# untitled.net
KiCad netlist of a schematic drawn in EAGLE
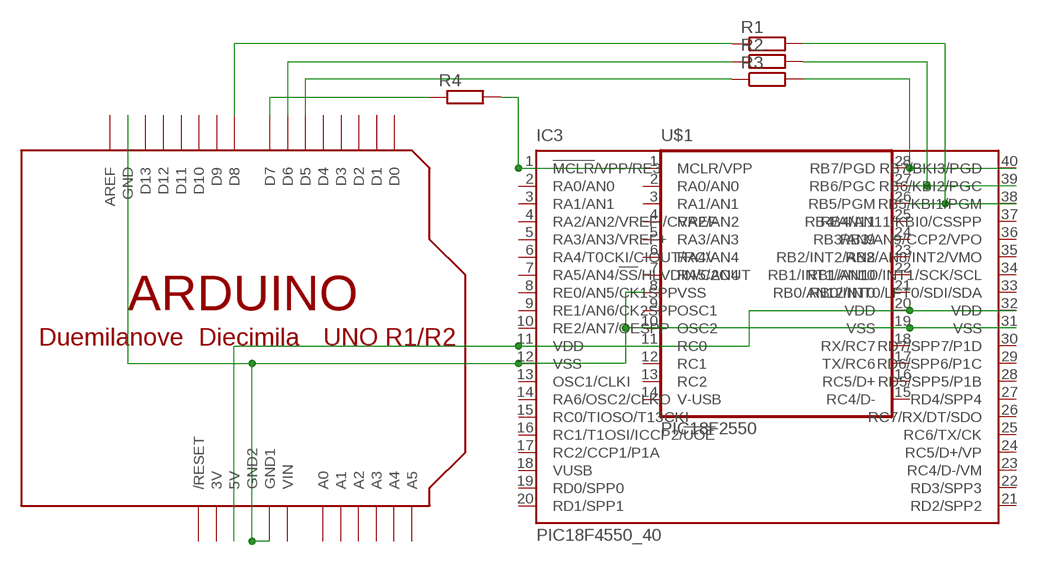
[diagram p0: schematic, sheet 1]

(export (version "E")
  (design (tool "Eeschema 10.0.6"))
  (components
    (comp (ref "IC3")
      (value "PIC18F4550_40")
      (footprint "eagle-import:DIL40")
      (fields (field (name "MF") "MICROCHIP") (field (name "MPN") "PIC18F4550-I/P"))
      (libsource (lib "eagle-import") (part "PIC18F4_40550"))
    )
    (comp (ref "R1")
      (value "R-EU_0204/7")
      (footprint "eagle-import:0204_7")
      (libsource (lib "eagle-import") (part "R-EU_0204/7"))
    )
    (comp (ref "R2")
      (value "R-EU_0204/7")
      (footprint "eagle-import:0204_7")
      (libsource (lib "eagle-import") (part "R-EU_0204/7"))
    )
    (comp (ref "R3")
      (value "R-EU_0204/7")
      (footprint "eagle-import:0204_7")
      (libsource (lib "eagle-import") (part "R-EU_0204/7"))
    )
    (comp (ref "R4")
      (value "R-EU_0204/7")
      (footprint "eagle-import:0204_7")
      (libsource (lib "eagle-import") (part "R-EU_0204/7"))
    )
    (comp (ref "U$1")
      (value "PIC18F2550")
      (footprint "eagle-import:DIL28-3")
      (libsource (lib "eagle-import") (part "PIC18F2550"))
    )
    (comp (ref "U$2")
      (value "ARDUINO-NOHOLE")
      (footprint "eagle-import:ARDUINO-NOHOLE")
      (libsource (lib "eagle-import") (part "ARDUINO-NOHOLE"))
    )
  )
  (nets
    (net (code "1") (name "/3V") (class "Default")
      (node (ref "U$2") (pin "3V") (pinfunction "3V_3V") (pintype "power_in"))
    )
    (net (code "2") (name "/VIN") (class "Default")
      (node (ref "U$2") (pin "VIN") (pinfunction "VIN_VIN") (pintype "power_in"))
    )
    (net (code "3") (name "Net-(IC3-RB5{slash}KBI1{slash}PGM)") (class "Default")
      (node (ref "IC3") (pin "38") (pinfunction "RB5/KBI1/PGM_38") (pintype "bidirectional"))
      (node (ref "R1") (pin "2") (pinfunction "2_2") (pintype "passive"))
      (node (ref "U$1") (pin "26") (pinfunction "RB5/PGM_26") (pintype "bidirectional"))
    )
    (net (code "4") (name "Net-(IC3-RB6{slash}KBI2{slash}PGC)") (class "Default")
      (node (ref "IC3") (pin "39") (pinfunction "RB6/KBI2/PGC_39") (pintype "bidirectional"))
      (node (ref "R2") (pin "2") (pinfunction "2_2") (pintype "passive"))
      (node (ref "U$1") (pin "27") (pinfunction "RB6/PGC_27") (pintype "bidirectional"))
    )
    (net (code "5") (name "Net-(IC3-RB7{slash}BKI3{slash}PGD)") (class "Default")
      (node (ref "IC3") (pin "40") (pinfunction "RB7/BKI3/PGD_40") (pintype "bidirectional"))
      (node (ref "R3") (pin "2") (pinfunction "2_2") (pintype "passive"))
      (node (ref "U$1") (pin "28") (pinfunction "RB7/PGD_28") (pintype "bidirectional"))
    )
    (net (code "6") (name "Net-(IC3-VSS-Pad12)") (class "Default")
      (node (ref "IC3") (pin "12") (pinfunction "VSS_12") (pintype "power_in"))
      (node (ref "IC3") (pin "31") (pinfunction "VSS_31") (pintype "power_in"))
      (node (ref "U$1") (pin "19") (pinfunction "VSS_19") (pintype "power_in"))
      (node (ref "U$1") (pin "8") (pinfunction "VSS_8") (pintype "power_in"))
      (node (ref "U$2") (pin "GND") (pinfunction "GND_GND") (pintype "power_in"))
      (node (ref "U$2") (pin "GND1") (pinfunction "GND1_GND1") (pintype "power_in"))
      (node (ref "U$2") (pin "GND2") (pinfunction "GND2_GND2") (pintype "power_in"))
    )
    (net (code "7") (name "Net-(IC3-~{MCLR}{slash}VPP{slash}RE3)") (class "Default")
      (node (ref "IC3") (pin "1") (pinfunction "~{MCLR}/VPP/RE3_1") (pintype "input"))
      (node (ref "R4") (pin "2") (pinfunction "2_2") (pintype "passive"))
      (node (ref "U$1") (pin "1") (pinfunction "MCLR/VPP_1") (pintype "bidirectional"))
    )
    (net (code "8") (name "Net-(R1-Pad1)") (class "Default")
      (node (ref "R1") (pin "1") (pinfunction "1_1") (pintype "passive"))
      (node (ref "U$2") (pin "D8") (pinfunction "D8_D8") (pintype "bidirectional"))
    )
    (net (code "9") (name "Net-(R2-Pad1)") (class "Default")
      (node (ref "R2") (pin "1") (pinfunction "1_1") (pintype "passive"))
      (node (ref "U$2") (pin "D6") (pinfunction "D6_D6") (pintype "bidirectional"))
    )
    (net (code "10") (name "Net-(R3-Pad1)") (class "Default")
      (node (ref "R3") (pin "1") (pinfunction "1_1") (pintype "passive"))
      (node (ref "U$2") (pin "D5") (pinfunction "D5_D5") (pintype "bidirectional"))
    )
    (net (code "11") (name "Net-(R4-Pad1)") (class "Default")
      (node (ref "R4") (pin "1") (pinfunction "1_1") (pintype "passive"))
      (node (ref "U$2") (pin "D7") (pinfunction "D7_D7") (pintype "bidirectional"))
    )
    (net (code "12") (name "Net-(U$1-VDD)") (class "Default")
      (node (ref "IC3") (pin "11") (pinfunction "VDD_11") (pintype "power_in"))
      (node (ref "IC3") (pin "32") (pinfunction "VDD_32") (pintype "power_in"))
      (node (ref "U$1") (pin "20") (pinfunction "VDD_20") (pintype "power_in"))
      (node (ref "U$2") (pin "5V") (pinfunction "5V_5V") (pintype "power_in"))
    )
    (net (code "13") (name "unconnected-(IC3-OSC1{slash}CLKI-Pad13)") (class "Default")
      (node (ref "IC3") (pin "13") (pinfunction "OSC1/CLKI_13") (pintype "input"))
    )
    (net (code "14") (name "unconnected-(IC3-RA0{slash}AN0-Pad2)") (class "Default")
      (node (ref "IC3") (pin "2") (pinfunction "RA0/AN0_2") (pintype "bidirectional"))
    )
    (net (code "15") (name "unconnected-(IC3-RA1{slash}AN1-Pad3)") (class "Default")
      (node (ref "IC3") (pin "3") (pinfunction "RA1/AN1_3") (pintype "bidirectional"))
    )
    (net (code "16") (name "unconnected-(IC3-RA2{slash}AN2{slash}VREF-{slash}CVREF-Pad4)") (class "Default")
      (node (ref "IC3") (pin "4") (pinfunction "RA2/AN2/VREF-/CVREF_4") (pintype "bidirectional"))
    )
    (net (code "17") (name "unconnected-(IC3-RA3{slash}AN3{slash}VREF+-Pad5)") (class "Default")
      (node (ref "IC3") (pin "5") (pinfunction "RA3/AN3/VREF+_5") (pintype "bidirectional"))
    )
    (net (code "18") (name "unconnected-(IC3-RA4{slash}T0CKI{slash}CIOUT{slash}RCV-Pad6)") (class "Default")
      (node (ref "IC3") (pin "6") (pinfunction "RA4/T0CKI/CIOUT/RCV_6") (pintype "bidirectional"))
    )
    (net (code "19") (name "unconnected-(IC3-RA5{slash}AN4{slash}~{SS}{slash}HLVDIN{slash}C2OUT-Pad7)") (class "Default")
      (node (ref "IC3") (pin "7") (pinfunction "RA5/AN4/~{SS}/HLVDIN/C2OUT_7") (pintype "bidirectional"))
    )
    (net (code "20") (name "unconnected-(IC3-RA6{slash}OSC2{slash}CLKO-Pad14)") (class "Default")
      (node (ref "IC3") (pin "14") (pinfunction "RA6/OSC2/CLKO_14") (pintype "output"))
    )
    (net (code "21") (name "unconnected-(IC3-RB0{slash}AN12{slash}INT0{slash}LFT0{slash}SDI{slash}SDA-Pad33)") (class "Default")
      (node (ref "IC3") (pin "33") (pinfunction "RB0/AN12/INT0/LFT0/SDI/SDA_33") (pintype "bidirectional"))
    )
    (net (code "22") (name "unconnected-(IC3-RB1{slash}AN10{slash}INT1{slash}SCK{slash}SCL-Pad34)") (class "Default")
      (node (ref "IC3") (pin "34") (pinfunction "RB1/AN10/INT1/SCK/SCL_34") (pintype "bidirectional"))
    )
    (net (code "23") (name "unconnected-(IC3-RB2{slash}AN8{slash}INT2{slash}VMO-Pad35)") (class "Default")
      (node (ref "IC3") (pin "35") (pinfunction "RB2/AN8/INT2/VMO_35") (pintype "bidirectional"))
    )
    (net (code "24") (name "unconnected-(IC3-RB3{slash}AN9{slash}CCP2{slash}VPO-Pad36)") (class "Default")
      (node (ref "IC3") (pin "36") (pinfunction "RB3/AN9/CCP2/VPO_36") (pintype "bidirectional"))
    )
    (net (code "25") (name "unconnected-(IC3-RB4{slash}AN11{slash}KBI0{slash}CSSPP-Pad37)") (class "Default")
      (node (ref "IC3") (pin "37") (pinfunction "RB4/AN11/KBI0/CSSPP_37") (pintype "bidirectional"))
    )
    (net (code "26") (name "unconnected-(IC3-RC0{slash}TIOSO{slash}T13CKI-Pad15)") (class "Default")
      (node (ref "IC3") (pin "15") (pinfunction "RC0/TIOSO/T13CKI_15") (pintype "bidirectional"))
    )
    (net (code "27") (name "unconnected-(IC3-RC1{slash}T1OSI{slash}ICCP2{slash}~{UOE}-Pad16)") (class "Default")
      (node (ref "IC3") (pin "16") (pinfunction "RC1/T1OSI/ICCP2/~{UOE}_16") (pintype "bidirectional"))
    )
    (net (code "28") (name "unconnected-(IC3-RC2{slash}CCP1{slash}P1A-Pad17)") (class "Default")
      (node (ref "IC3") (pin "17") (pinfunction "RC2/CCP1/P1A_17") (pintype "bidirectional"))
    )
    (net (code "29") (name "unconnected-(IC3-RC4{slash}D-{slash}VM-Pad23)") (class "Default")
      (node (ref "IC3") (pin "23") (pinfunction "RC4/D-/VM_23") (pintype "bidirectional"))
    )
    (net (code "30") (name "unconnected-(IC3-RC5{slash}D+{slash}VP-Pad24)") (class "Default")
      (node (ref "IC3") (pin "24") (pinfunction "RC5/D+/VP_24") (pintype "bidirectional"))
    )
    (net (code "31") (name "unconnected-(IC3-RC6{slash}TX{slash}CK-Pad25)") (class "Default")
      (node (ref "IC3") (pin "25") (pinfunction "RC6/TX/CK_25") (pintype "bidirectional"))
    )
    (net (code "32") (name "unconnected-(IC3-RC7{slash}RX{slash}DT{slash}SDO-Pad26)") (class "Default")
      (node (ref "IC3") (pin "26") (pinfunction "RC7/RX/DT/SDO_26") (pintype "bidirectional"))
    )
    (net (code "33") (name "unconnected-(IC3-RD0{slash}SPP0-Pad19)") (class "Default")
      (node (ref "IC3") (pin "19") (pinfunction "RD0/SPP0_19") (pintype "bidirectional"))
    )
    (net (code "34") (name "unconnected-(IC3-RD1{slash}SPP1-Pad20)") (class "Default")
      (node (ref "IC3") (pin "20") (pinfunction "RD1/SPP1_20") (pintype "bidirectional"))
    )
    (net (code "35") (name "unconnected-(IC3-RD2{slash}SPP2-Pad21)") (class "Default")
      (node (ref "IC3") (pin "21") (pinfunction "RD2/SPP2_21") (pintype "bidirectional"))
    )
    (net (code "36") (name "unconnected-(IC3-RD3{slash}SPP3-Pad22)") (class "Default")
      (node (ref "IC3") (pin "22") (pinfunction "RD3/SPP3_22") (pintype "bidirectional"))
    )
    (net (code "37") (name "unconnected-(IC3-RD4{slash}SPP4-Pad27)") (class "Default")
      (node (ref "IC3") (pin "27") (pinfunction "RD4/SPP4_27") (pintype "bidirectional"))
    )
    (net (code "38") (name "unconnected-(IC3-RD5{slash}SPP5{slash}P1B-Pad28)") (class "Default")
      (node (ref "IC3") (pin "28") (pinfunction "RD5/SPP5/P1B_28") (pintype "bidirectional"))
    )
    (net (code "39") (name "unconnected-(IC3-RD6{slash}SPP6{slash}P1C-Pad29)") (class "Default")
      (node (ref "IC3") (pin "29") (pinfunction "RD6/SPP6/P1C_29") (pintype "bidirectional"))
    )
    (net (code "40") (name "unconnected-(IC3-RD7{slash}SPP7{slash}P1D-Pad30)") (class "Default")
      (node (ref "IC3") (pin "30") (pinfunction "RD7/SPP7/P1D_30") (pintype "bidirectional"))
    )
    (net (code "41") (name "unconnected-(IC3-RE0{slash}AN5{slash}CK1SPP-Pad8)") (class "Default")
      (node (ref "IC3") (pin "8") (pinfunction "RE0/AN5/CK1SPP_8") (pintype "bidirectional"))
    )
    (net (code "42") (name "unconnected-(IC3-RE1{slash}AN6{slash}CK2SPP-Pad9)") (class "Default")
      (node (ref "IC3") (pin "9") (pinfunction "RE1/AN6/CK2SPP_9") (pintype "bidirectional"))
    )
    (net (code "43") (name "unconnected-(IC3-RE2{slash}AN7{slash}OESPP-Pad10)") (class "Default")
      (node (ref "IC3") (pin "10") (pinfunction "RE2/AN7/OESPP_10") (pintype "bidirectional"))
    )
    (net (code "44") (name "unconnected-(IC3-VUSB-Pad18)") (class "Default")
      (node (ref "IC3") (pin "18") (pinfunction "VUSB_18") (pintype "bidirectional"))
    )
    (net (code "45") (name "unconnected-(U$1-OSC1-Pad9)") (class "Default")
      (node (ref "U$1") (pin "9") (pinfunction "OSC1_9") (pintype "bidirectional"))
    )
    (net (code "46") (name "unconnected-(U$1-OSC2-Pad10)") (class "Default")
      (node (ref "U$1") (pin "10") (pinfunction "OSC2_10") (pintype "bidirectional"))
    )
    (net (code "47") (name "unconnected-(U$1-RA0{slash}AN0-Pad2)") (class "Default")
      (node (ref "U$1") (pin "2") (pinfunction "RA0/AN0_2") (pintype "bidirectional"))
    )
    (net (code "48") (name "unconnected-(U$1-RA1{slash}AN1-Pad3)") (class "Default")
      (node (ref "U$1") (pin "3") (pinfunction "RA1/AN1_3") (pintype "bidirectional"))
    )
    (net (code "49") (name "unconnected-(U$1-RA2{slash}AN2-Pad4)") (class "Default")
      (node (ref "U$1") (pin "4") (pinfunction "RA2/AN2_4") (pintype "bidirectional"))
    )
    (net (code "50") (name "unconnected-(U$1-RA3{slash}AN3-Pad5)") (class "Default")
      (node (ref "U$1") (pin "5") (pinfunction "RA3/AN3_5") (pintype "bidirectional"))
    )
    (net (code "51") (name "unconnected-(U$1-RA4{slash}AN4-Pad6)") (class "Default")
      (node (ref "U$1") (pin "6") (pinfunction "RA4/AN4_6") (pintype "bidirectional"))
    )
    (net (code "52") (name "unconnected-(U$1-RA5{slash}AN4-Pad7)") (class "Default")
      (node (ref "U$1") (pin "7") (pinfunction "RA5/AN4_7") (pintype "bidirectional"))
    )
    (net (code "53") (name "unconnected-(U$1-RB0{slash}INT0-Pad21)") (class "Default")
      (node (ref "U$1") (pin "21") (pinfunction "RB0/INT0_21") (pintype "bidirectional"))
    )
    (net (code "54") (name "unconnected-(U$1-RB1{slash}INT1{slash}AN10-Pad22)") (class "Default")
      (node (ref "U$1") (pin "22") (pinfunction "RB1/INT1/AN10_22") (pintype "bidirectional"))
    )
    (net (code "55") (name "unconnected-(U$1-RB2{slash}INT2{slash}AN8-Pad23)") (class "Default")
      (node (ref "U$1") (pin "23") (pinfunction "RB2/INT2/AN8_23") (pintype "bidirectional"))
    )
    (net (code "56") (name "unconnected-(U$1-RB3{slash}AN9-Pad24)") (class "Default")
      (node (ref "U$1") (pin "24") (pinfunction "RB3/AN9_24") (pintype "bidirectional"))
    )
    (net (code "57") (name "unconnected-(U$1-RB4{slash}AN11-Pad25)") (class "Default")
      (node (ref "U$1") (pin "25") (pinfunction "RB4/AN11_25") (pintype "bidirectional"))
    )
    (net (code "58") (name "unconnected-(U$1-RC0-Pad11)") (class "Default")
      (node (ref "U$1") (pin "11") (pinfunction "RC0_11") (pintype "bidirectional"))
    )
    (net (code "59") (name "unconnected-(U$1-RC1-Pad12)") (class "Default")
      (node (ref "U$1") (pin "12") (pinfunction "RC1_12") (pintype "bidirectional"))
    )
    (net (code "60") (name "unconnected-(U$1-RC2-Pad13)") (class "Default")
      (node (ref "U$1") (pin "13") (pinfunction "RC2_13") (pintype "bidirectional"))
    )
    (net (code "61") (name "unconnected-(U$1-RC4{slash}D--Pad15)") (class "Default")
      (node (ref "U$1") (pin "15") (pinfunction "RC4/D-_15") (pintype "bidirectional"))
    )
    (net (code "62") (name "unconnected-(U$1-RC5{slash}D+-Pad16)") (class "Default")
      (node (ref "U$1") (pin "16") (pinfunction "RC5/D+_16") (pintype "bidirectional"))
    )
    (net (code "63") (name "unconnected-(U$1-RX{slash}RC7-Pad18)") (class "Default")
      (node (ref "U$1") (pin "18") (pinfunction "RX/RC7_18") (pintype "input"))
    )
    (net (code "64") (name "unconnected-(U$1-TX{slash}RC6-Pad17)") (class "Default")
      (node (ref "U$1") (pin "17") (pinfunction "TX/RC6_17") (pintype "bidirectional"))
    )
    (net (code "65") (name "unconnected-(U$1-V-USB-Pad14)") (class "Default")
      (node (ref "U$1") (pin "14") (pinfunction "V-USB_14") (pintype "bidirectional"))
    )
    (net (code "66") (name "unconnected-(U$2-PadA0)") (class "Default")
      (node (ref "U$2") (pin "A0") (pinfunction "A0_A0") (pintype "bidirectional"))
    )
    (net (code "67") (name "unconnected-(U$2-PadA1)") (class "Default")
      (node (ref "U$2") (pin "A1") (pinfunction "A1_A1") (pintype "bidirectional"))
    )
    (net (code "68") (name "unconnected-(U$2-PadA2)") (class "Default")
      (node (ref "U$2") (pin "A2") (pinfunction "A2_A2") (pintype "bidirectional"))
    )
    (net (code "69") (name "unconnected-(U$2-PadA3)") (class "Default")
      (node (ref "U$2") (pin "A3") (pinfunction "A3_A3") (pintype "bidirectional"))
    )
    (net (code "70") (name "unconnected-(U$2-PadA4)") (class "Default")
      (node (ref "U$2") (pin "A4") (pinfunction "A4_A4") (pintype "bidirectional"))
    )
    (net (code "71") (name "unconnected-(U$2-PadA5)") (class "Default")
      (node (ref "U$2") (pin "A5") (pinfunction "A5_A5") (pintype "bidirectional"))
    )
    (net (code "72") (name "unconnected-(U$2-PadAREF)") (class "Default")
      (node (ref "U$2") (pin "AREF") (pinfunction "AREF_AREF") (pintype "bidirectional"))
    )
    (net (code "73") (name "unconnected-(U$2-PadD0)") (class "Default")
      (node (ref "U$2") (pin "D0") (pinfunction "D0_D0") (pintype "bidirectional"))
    )
    (net (code "74") (name "unconnected-(U$2-PadD1)") (class "Default")
      (node (ref "U$2") (pin "D1") (pinfunction "D1_D1") (pintype "bidirectional"))
    )
    (net (code "75") (name "unconnected-(U$2-PadD2)") (class "Default")
      (node (ref "U$2") (pin "D2") (pinfunction "D2_D2") (pintype "bidirectional"))
    )
    (net (code "76") (name "unconnected-(U$2-PadD3)") (class "Default")
      (node (ref "U$2") (pin "D3") (pinfunction "D3_D3") (pintype "bidirectional"))
    )
    (net (code "77") (name "unconnected-(U$2-PadD4)") (class "Default")
      (node (ref "U$2") (pin "D4") (pinfunction "D4_D4") (pintype "bidirectional"))
    )
    (net (code "78") (name "unconnected-(U$2-PadD9)") (class "Default")
      (node (ref "U$2") (pin "D9") (pinfunction "D9_D9") (pintype "bidirectional"))
    )
    (net (code "79") (name "unconnected-(U$2-PadD10)") (class "Default")
      (node (ref "U$2") (pin "D10") (pinfunction "D10_D10") (pintype "bidirectional"))
    )
    (net (code "80") (name "unconnected-(U$2-PadD11)") (class "Default")
      (node (ref "U$2") (pin "D11") (pinfunction "D11_D11") (pintype "bidirectional"))
    )
    (net (code "81") (name "unconnected-(U$2-PadD12)") (class "Default")
      (node (ref "U$2") (pin "D12") (pinfunction "D12_D12") (pintype "bidirectional"))
    )
    (net (code "82") (name "unconnected-(U$2-PadD13)") (class "Default")
      (node (ref "U$2") (pin "D13") (pinfunction "D13_D13") (pintype "bidirectional"))
    )
    (net (code "83") (name "unconnected-(U$2-{slash}RESET-PadRESET)") (class "Default")
      (node (ref "U$2") (pin "RESET") (pinfunction "/RESET_RESET") (pintype "bidirectional"))
    )
  )
)
